# Bottom_PCB.net
KiCad netlist of a schematic drawn in EAGLE
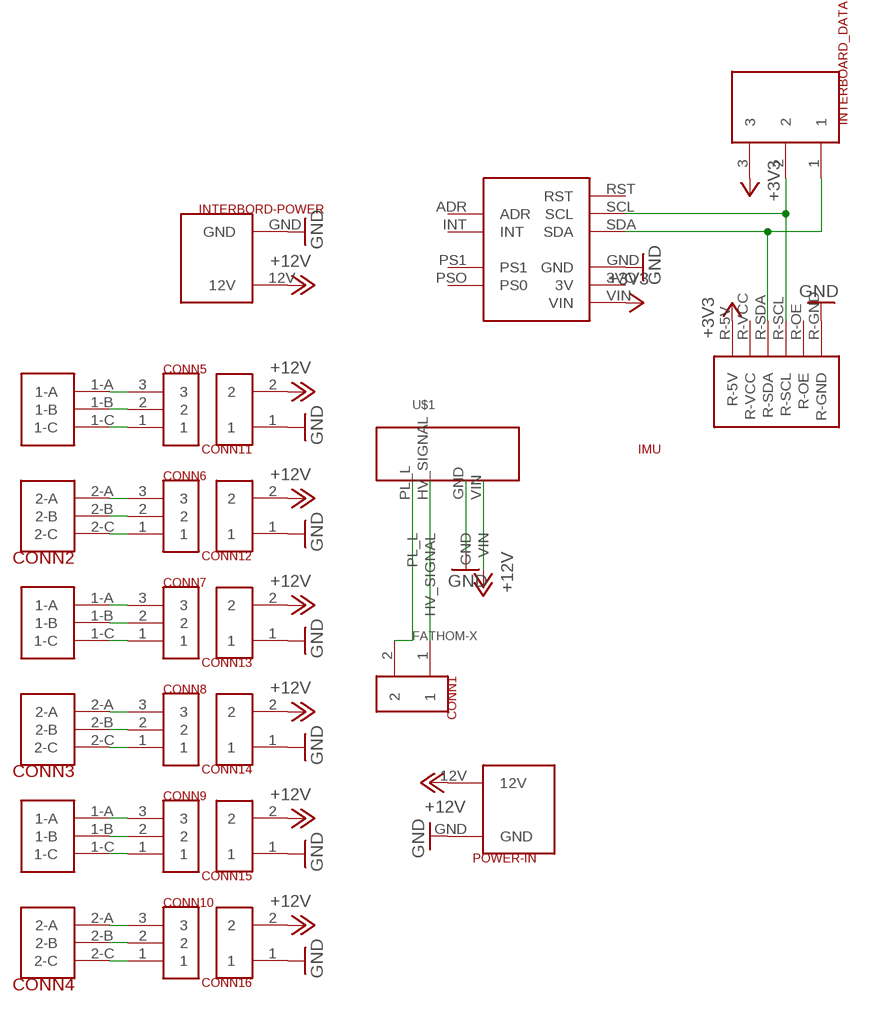
[diagram p0: schematic, sheet 1]

(export (version "E")
  (design (tool "Eeschema 10.0.6"))
  (components
    (comp (ref "CONN1")
      (value "2CONTACT_ULTRAFIT_R/A")
      (footprint "eagle-import:2CONTAC_ULTRAFIT_R_A")
      (libsource (lib "eagle-import") (part "2CONTACT_ULTRAFIT_R/A"))
    )
    (comp (ref "CONN2")
      (value "6CONTACT_ULTRAFIT_R/A")
      (footprint "eagle-import:6CONTACT_ULTRAFIT_R_A")
      (libsource (lib "eagle-import") (part "6CONTACT_ULTRAFIT_R/A"))
    )
    (comp (ref "CONN3")
      (value "6CONTACT_ULTRAFIT_R/A")
      (footprint "eagle-import:6CONTACT_ULTRAFIT_R_A")
      (libsource (lib "eagle-import") (part "6CONTACT_ULTRAFIT_R/A"))
    )
    (comp (ref "CONN4")
      (value "6CONTACT_ULTRAFIT_R/A")
      (footprint "eagle-import:6CONTACT_ULTRAFIT_R_A")
      (libsource (lib "eagle-import") (part "6CONTACT_ULTRAFIT_R/A"))
    )
    (comp (ref "CONN5")
      (value "3CONTACT_ULTRAFIT_VERT")
      (footprint "eagle-import:3CONTAC_ULTRAFIT_VERT")
      (libsource (lib "eagle-import") (part "3CONTACT_ULTRAFIT_VERT"))
    )
    (comp (ref "CONN6")
      (value "3CONTACT_ULTRAFIT_VERT")
      (footprint "eagle-import:3CONTAC_ULTRAFIT_VERT")
      (libsource (lib "eagle-import") (part "3CONTACT_ULTRAFIT_VERT"))
    )
    (comp (ref "CONN7")
      (value "3CONTACT_ULTRAFIT_VERT")
      (footprint "eagle-import:3CONTAC_ULTRAFIT_VERT")
      (libsource (lib "eagle-import") (part "3CONTACT_ULTRAFIT_VERT"))
    )
    (comp (ref "CONN8")
      (value "3CONTACT_ULTRAFIT_VERT")
      (footprint "eagle-import:3CONTAC_ULTRAFIT_VERT")
      (libsource (lib "eagle-import") (part "3CONTACT_ULTRAFIT_VERT"))
    )
    (comp (ref "CONN9")
      (value "3CONTACT_ULTRAFIT_VERT")
      (footprint "eagle-import:3CONTAC_ULTRAFIT_VERT")
      (libsource (lib "eagle-import") (part "3CONTACT_ULTRAFIT_VERT"))
    )
    (comp (ref "CONN10")
      (value "3CONTACT_ULTRAFIT_VERT")
      (footprint "eagle-import:3CONTAC_ULTRAFIT_VERT")
      (libsource (lib "eagle-import") (part "3CONTACT_ULTRAFIT_VERT"))
    )
    (comp (ref "CONN11")
      (value "2CONTACT_ULTRAFIT_VERT")
      (footprint "eagle-import:2CONTAC_ULTRAFIT_VERT")
      (libsource (lib "eagle-import") (part "2CONTACT_ULTRAFIT_VERT"))
    )
    (comp (ref "CONN12")
      (value "2CONTACT_ULTRAFIT_VERT")
      (footprint "eagle-import:2CONTAC_ULTRAFIT_VERT")
      (libsource (lib "eagle-import") (part "2CONTACT_ULTRAFIT_VERT"))
    )
    (comp (ref "CONN13")
      (value "2CONTACT_ULTRAFIT_VERT")
      (footprint "eagle-import:2CONTAC_ULTRAFIT_VERT")
      (libsource (lib "eagle-import") (part "2CONTACT_ULTRAFIT_VERT"))
    )
    (comp (ref "CONN14")
      (value "2CONTACT_ULTRAFIT_VERT")
      (footprint "eagle-import:2CONTAC_ULTRAFIT_VERT")
      (libsource (lib "eagle-import") (part "2CONTACT_ULTRAFIT_VERT"))
    )
    (comp (ref "CONN15")
      (value "2CONTACT_ULTRAFIT_VERT")
      (footprint "eagle-import:2CONTAC_ULTRAFIT_VERT")
      (libsource (lib "eagle-import") (part "2CONTACT_ULTRAFIT_VERT"))
    )
    (comp (ref "CONN16")
      (value "2CONTACT_ULTRAFIT_VERT")
      (footprint "eagle-import:2CONTAC_ULTRAFIT_VERT")
      (libsource (lib "eagle-import") (part "2CONTACT_ULTRAFIT_VERT"))
    )
    (comp (ref "IMU")
      (value "IMU")
      (footprint "eagle-import:IMU")
      (libsource (lib "eagle-import") (part "IMU"))
    )
    (comp (ref "INTERBOARD_DATA")
      (value "3CONTAC_ULTRAFIT_R/A")
      (footprint "eagle-import:3CONTAC_ULTRAFIT_R_A")
      (libsource (lib "eagle-import") (part "3CONTAC_ULTRAFIT_R/A"))
    )
    (comp (ref "INTERBORD-POWER")
      (value "2-CONTACT-SUPER")
      (footprint "eagle-import:2-CONTACT-SUPER")
      (libsource (lib "eagle-import") (part "2-CONTACT-SUPER"))
    )
    (comp (ref "POWER-IN")
      (value "2-CONTACT-SUPER")
      (footprint "eagle-import:2-CONTACT-SUPER")
      (libsource (lib "eagle-import") (part "2-CONTACT-SUPER"))
    )
    (comp (ref "PWM1")
      (value "PWM_EXTENDER-SIMPLE")
      (footprint "eagle-import:PWM_EXTENDER-SIMPLE")
      (libsource (lib "eagle-import") (part "PWM_EXTENDER-SIMPLE"))
    )
    (comp (ref "U$1")
      (value "FATHOM-X")
      (footprint "eagle-import:FATHOM-X")
      (libsource (lib "eagle-import") (part "FATHOM-X"))
    )
  )
  (nets
    (net (code "1") (name "+3V3") (class "Default")
      (node (ref "IMU") (pin "VIN") (pinfunction "VIN_VIN") (pintype "bidirectional"))
      (node (ref "INTERBOARD_DATA") (pin "3") (pinfunction "3_3") (pintype "bidirectional"))
      (node (ref "PWM1") (pin "R-5V") (pinfunction "R-5V_R-5V") (pintype "bidirectional"))
    )
    (net (code "2") (name "+12V") (class "Default")
      (node (ref "CONN11") (pin "2") (pinfunction "2_2") (pintype "bidirectional"))
      (node (ref "CONN12") (pin "2") (pinfunction "2_2") (pintype "bidirectional"))
      (node (ref "CONN13") (pin "2") (pinfunction "2_2") (pintype "bidirectional"))
      (node (ref "CONN14") (pin "2") (pinfunction "2_2") (pintype "bidirectional"))
      (node (ref "CONN15") (pin "2") (pinfunction "2_2") (pintype "bidirectional"))
      (node (ref "CONN16") (pin "2") (pinfunction "2_2") (pintype "bidirectional"))
      (node (ref "INTERBORD-POWER") (pin "12V") (pinfunction "12V_12V") (pintype "bidirectional"))
      (node (ref "POWER-IN") (pin "12V") (pinfunction "12V_12V") (pintype "bidirectional"))
      (node (ref "U$1") (pin "VIN") (pinfunction "VIN_VIN") (pintype "bidirectional"))
    )
    (net (code "3") (name "GND") (class "Default")
      (node (ref "CONN11") (pin "1") (pinfunction "1_1") (pintype "bidirectional"))
      (node (ref "CONN12") (pin "1") (pinfunction "1_1") (pintype "bidirectional"))
      (node (ref "CONN13") (pin "1") (pinfunction "1_1") (pintype "bidirectional"))
      (node (ref "CONN14") (pin "1") (pinfunction "1_1") (pintype "bidirectional"))
      (node (ref "CONN15") (pin "1") (pinfunction "1_1") (pintype "bidirectional"))
      (node (ref "CONN16") (pin "1") (pinfunction "1_1") (pintype "bidirectional"))
      (node (ref "IMU") (pin "GND") (pinfunction "GND_GND") (pintype "bidirectional"))
      (node (ref "INTERBORD-POWER") (pin "GND") (pinfunction "GND_GND") (pintype "bidirectional"))
      (node (ref "POWER-IN") (pin "GND") (pinfunction "GND_GND") (pintype "bidirectional"))
      (node (ref "PWM1") (pin "R-GND") (pinfunction "R-GND_R-GND") (pintype "bidirectional"))
      (node (ref "U$1") (pin "GND") (pinfunction "GND_GND") (pintype "bidirectional"))
    )
    (net (code "4") (name "Net-(CONN1-Pad1)") (class "Default")
      (node (ref "CONN1") (pin "1") (pinfunction "1_1") (pintype "bidirectional"))
      (node (ref "U$1") (pin "HV_SIGNAL") (pinfunction "HV_SIGNAL_HV_SIGNAL") (pintype "bidirectional"))
    )
    (net (code "5") (name "Net-(CONN1-Pad2)") (class "Default")
      (node (ref "CONN1") (pin "2") (pinfunction "2_2") (pintype "bidirectional"))
      (node (ref "U$1") (pin "PL_L") (pinfunction "PL_L_PL_L") (pintype "bidirectional"))
    )
    (net (code "6") (name "Net-(CONN2-Pad1-A)") (class "Default")
      (node (ref "CONN2") (pin "1-A") (pinfunction "1-A_1-A") (pintype "bidirectional"))
      (node (ref "CONN5") (pin "3") (pinfunction "3_3") (pintype "bidirectional"))
    )
    (net (code "7") (name "Net-(CONN2-Pad1-B)") (class "Default")
      (node (ref "CONN2") (pin "1-B") (pinfunction "1-B_1-B") (pintype "bidirectional"))
      (node (ref "CONN5") (pin "2") (pinfunction "2_2") (pintype "bidirectional"))
    )
    (net (code "8") (name "Net-(CONN2-Pad1-C)") (class "Default")
      (node (ref "CONN2") (pin "1-C") (pinfunction "1-C_1-C") (pintype "bidirectional"))
      (node (ref "CONN5") (pin "1") (pinfunction "1_1") (pintype "bidirectional"))
    )
    (net (code "9") (name "Net-(CONN2-Pad2-A)") (class "Default")
      (node (ref "CONN2") (pin "2-A") (pinfunction "2-A_2-A") (pintype "bidirectional"))
      (node (ref "CONN6") (pin "3") (pinfunction "3_3") (pintype "bidirectional"))
    )
    (net (code "10") (name "Net-(CONN2-Pad2-B)") (class "Default")
      (node (ref "CONN2") (pin "2-B") (pinfunction "2-B_2-B") (pintype "bidirectional"))
      (node (ref "CONN6") (pin "2") (pinfunction "2_2") (pintype "bidirectional"))
    )
    (net (code "11") (name "Net-(CONN2-Pad2-C)") (class "Default")
      (node (ref "CONN2") (pin "2-C") (pinfunction "2-C_2-C") (pintype "bidirectional"))
      (node (ref "CONN6") (pin "1") (pinfunction "1_1") (pintype "bidirectional"))
    )
    (net (code "12") (name "Net-(CONN3-Pad1-A)") (class "Default")
      (node (ref "CONN3") (pin "1-A") (pinfunction "1-A_1-A") (pintype "bidirectional"))
      (node (ref "CONN7") (pin "3") (pinfunction "3_3") (pintype "bidirectional"))
    )
    (net (code "13") (name "Net-(CONN3-Pad1-B)") (class "Default")
      (node (ref "CONN3") (pin "1-B") (pinfunction "1-B_1-B") (pintype "bidirectional"))
      (node (ref "CONN7") (pin "2") (pinfunction "2_2") (pintype "bidirectional"))
    )
    (net (code "14") (name "Net-(CONN3-Pad1-C)") (class "Default")
      (node (ref "CONN3") (pin "1-C") (pinfunction "1-C_1-C") (pintype "bidirectional"))
      (node (ref "CONN7") (pin "1") (pinfunction "1_1") (pintype "bidirectional"))
    )
    (net (code "15") (name "Net-(CONN3-Pad2-A)") (class "Default")
      (node (ref "CONN3") (pin "2-A") (pinfunction "2-A_2-A") (pintype "bidirectional"))
      (node (ref "CONN8") (pin "3") (pinfunction "3_3") (pintype "bidirectional"))
    )
    (net (code "16") (name "Net-(CONN3-Pad2-B)") (class "Default")
      (node (ref "CONN3") (pin "2-B") (pinfunction "2-B_2-B") (pintype "bidirectional"))
      (node (ref "CONN8") (pin "2") (pinfunction "2_2") (pintype "bidirectional"))
    )
    (net (code "17") (name "Net-(CONN3-Pad2-C)") (class "Default")
      (node (ref "CONN3") (pin "2-C") (pinfunction "2-C_2-C") (pintype "bidirectional"))
      (node (ref "CONN8") (pin "1") (pinfunction "1_1") (pintype "bidirectional"))
    )
    (net (code "18") (name "Net-(CONN4-Pad1-A)") (class "Default")
      (node (ref "CONN4") (pin "1-A") (pinfunction "1-A_1-A") (pintype "bidirectional"))
      (node (ref "CONN9") (pin "3") (pinfunction "3_3") (pintype "bidirectional"))
    )
    (net (code "19") (name "Net-(CONN4-Pad1-B)") (class "Default")
      (node (ref "CONN4") (pin "1-B") (pinfunction "1-B_1-B") (pintype "bidirectional"))
      (node (ref "CONN9") (pin "2") (pinfunction "2_2") (pintype "bidirectional"))
    )
    (net (code "20") (name "Net-(CONN4-Pad1-C)") (class "Default")
      (node (ref "CONN4") (pin "1-C") (pinfunction "1-C_1-C") (pintype "bidirectional"))
      (node (ref "CONN9") (pin "1") (pinfunction "1_1") (pintype "bidirectional"))
    )
    (net (code "21") (name "Net-(CONN10-Pad1)") (class "Default")
      (node (ref "CONN10") (pin "1") (pinfunction "1_1") (pintype "bidirectional"))
      (node (ref "CONN4") (pin "2-C") (pinfunction "2-C_2-C") (pintype "bidirectional"))
    )
    (net (code "22") (name "Net-(CONN10-Pad2)") (class "Default")
      (node (ref "CONN10") (pin "2") (pinfunction "2_2") (pintype "bidirectional"))
      (node (ref "CONN4") (pin "2-B") (pinfunction "2-B_2-B") (pintype "bidirectional"))
    )
    (net (code "23") (name "Net-(CONN10-Pad3)") (class "Default")
      (node (ref "CONN10") (pin "3") (pinfunction "3_3") (pintype "bidirectional"))
      (node (ref "CONN4") (pin "2-A") (pinfunction "2-A_2-A") (pintype "bidirectional"))
    )
    (net (code "24") (name "Net-(IMU-PadSCL)") (class "Default")
      (node (ref "IMU") (pin "SCL") (pinfunction "SCL_SCL") (pintype "bidirectional"))
      (node (ref "INTERBOARD_DATA") (pin "2") (pinfunction "2_2") (pintype "bidirectional"))
      (node (ref "PWM1") (pin "R-SCL") (pinfunction "R-SCL_R-SCL") (pintype "bidirectional"))
    )
    (net (code "25") (name "Net-(IMU-PadSDA)") (class "Default")
      (node (ref "IMU") (pin "SDA") (pinfunction "SDA_SDA") (pintype "bidirectional"))
      (node (ref "INTERBOARD_DATA") (pin "1") (pinfunction "1_1") (pintype "bidirectional"))
      (node (ref "PWM1") (pin "R-SDA") (pinfunction "R-SDA_R-SDA") (pintype "bidirectional"))
    )
    (net (code "26") (name "unconnected-(IMU-3V-Pad3VO)") (class "Default")
      (node (ref "IMU") (pin "3VO") (pinfunction "3V_3VO") (pintype "bidirectional"))
    )
    (net (code "27") (name "unconnected-(IMU-PS0-PadPSO)") (class "Default")
      (node (ref "IMU") (pin "PSO") (pinfunction "PS0_PSO") (pintype "bidirectional"))
    )
    (net (code "28") (name "unconnected-(IMU-PadADR)") (class "Default")
      (node (ref "IMU") (pin "ADR") (pinfunction "ADR_ADR") (pintype "bidirectional"))
    )
    (net (code "29") (name "unconnected-(IMU-PadINT)") (class "Default")
      (node (ref "IMU") (pin "INT") (pinfunction "INT_INT") (pintype "bidirectional"))
    )
    (net (code "30") (name "unconnected-(IMU-PadPS1)") (class "Default")
      (node (ref "IMU") (pin "PS1") (pinfunction "PS1_PS1") (pintype "bidirectional"))
    )
    (net (code "31") (name "unconnected-(IMU-PadRST)") (class "Default")
      (node (ref "IMU") (pin "RST") (pinfunction "RST_RST") (pintype "bidirectional"))
    )
    (net (code "32") (name "unconnected-(PWM1-PadR-OE)") (class "Default")
      (node (ref "PWM1") (pin "R-OE") (pinfunction "R-OE_R-OE") (pintype "bidirectional"))
    )
    (net (code "33") (name "unconnected-(PWM1-PadR-VCC)") (class "Default")
      (node (ref "PWM1") (pin "R-VCC") (pinfunction "R-VCC_R-VCC") (pintype "bidirectional"))
    )
  )
)
